# TEMP_SENS.net
KiCad netlist of a schematic drawn in Altium Designer
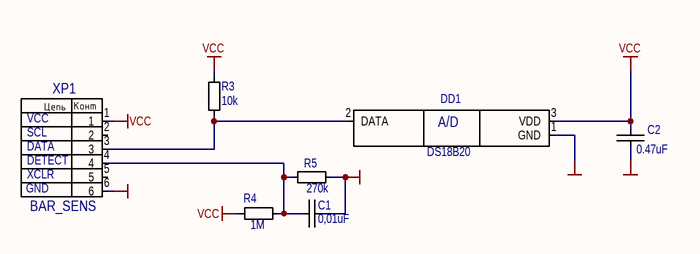
[diagram p0: TEMP_SENS.SchDoc]

(export (version "E")
  (design (tool "Eeschema 10.0.6"))
  (components
    (comp (ref "C1")
      (value "0,01uF")
      (footprint "Cap_0805")
      (fields (field (name "MANUFACTURER") "AVX") (field (name "PART NUMBER") "08055C103JAT2A"))
      (libsource (lib "PANEL") (part "Cap_0805"))
    )
    (comp (ref "C2")
      (value "0.47uF")
      (footprint "Cap_0805")
      (fields (field (name "MANUFACTURER") "AVX") (field (name "PART NUMBER") "0805YC475KAT2A"))
      (libsource (lib "PANEL") (part "Cap_0805"))
    )
    (comp (ref "DD1") (value "DS18B20") (footprint "DS18B20") (libsource (lib "TEMP_SENS") (part "DS18B20")))
    (comp (ref "R3")
      (value "10k")
      (footprint "Res_0805")
      (fields (field (name "MANUFACTURER") "Vishay"))
      (libsource (lib "") (part "Res_0805_1"))
    )
    (comp (ref "R4")
      (value "1M")
      (footprint "Res_0805")
      (fields (field (name "MANUFACTURER") "Vishay"))
      (libsource (lib "PANEL") (part "Res_0805"))
    )
    (comp (ref "R5")
      (value "270k")
      (footprint "Res_0805")
      (fields (field (name "MANUFACTURER") "Vishay"))
      (libsource (lib "PANEL") (part "Res_0805"))
    )
    (comp (ref "XP1")
      (value "BAR_SENS")
      (footprint "SENS_LEGS")
      (libsource (lib "BAR_SENS") (part "BAR_SENS"))
    )
  )
  (nets
    (net (code "1") (name "GND") (class "Default")
      (node (ref "C1") (pin "2") (pinfunction "2_2") (pintype "passive"))
      (node (ref "C2") (pin "1") (pinfunction "1_1") (pintype "passive"))
      (node (ref "DD1") (pin "1") (pinfunction "GND_1") (pintype "passive"))
      (node (ref "R5") (pin "1") (pinfunction "1_1") (pintype "passive"))
      (node (ref "XP1") (pin "6") (pinfunction "6_6") (pintype "passive"))
    )
    (net (code "2") (name "Net-(C1-Pad1)") (class "Default")
      (node (ref "C1") (pin "1") (pinfunction "1_1") (pintype "passive"))
      (node (ref "R4") (pin "1") (pinfunction "1_1") (pintype "passive"))
      (node (ref "R5") (pin "2") (pinfunction "2_2") (pintype "passive"))
      (node (ref "XP1") (pin "4") (pinfunction "4_4") (pintype "passive"))
    )
    (net (code "3") (name "Net-(DD1-DATA)") (class "Default")
      (node (ref "DD1") (pin "2") (pinfunction "DATA_2") (pintype "passive"))
      (node (ref "R3") (pin "2") (pinfunction "2_2") (pintype "passive"))
      (node (ref "XP1") (pin "3") (pinfunction "3_3") (pintype "passive"))
    )
    (net (code "4") (name "VCC") (class "Default")
      (node (ref "C2") (pin "2") (pinfunction "2_2") (pintype "passive"))
      (node (ref "DD1") (pin "3") (pinfunction "VDD_3") (pintype "passive"))
      (node (ref "R3") (pin "1") (pinfunction "1_1") (pintype "passive"))
      (node (ref "R4") (pin "2") (pinfunction "2_2") (pintype "passive"))
      (node (ref "XP1") (pin "1") (pinfunction "1_1") (pintype "passive"))
    )
    (net (code "5") (name "unconnected-(XP1-Pad2)") (class "Default")
      (node (ref "XP1") (pin "2") (pinfunction "2_2") (pintype "passive"))
    )
    (net (code "6") (name "unconnected-(XP1-Pad5)") (class "Default")
      (node (ref "XP1") (pin "5") (pinfunction "5_5") (pintype "passive"))
    )
  )
)
